# Sheet1_ESP32_Blynh.net
KiCad netlist of a schematic drawn in Altium Designer
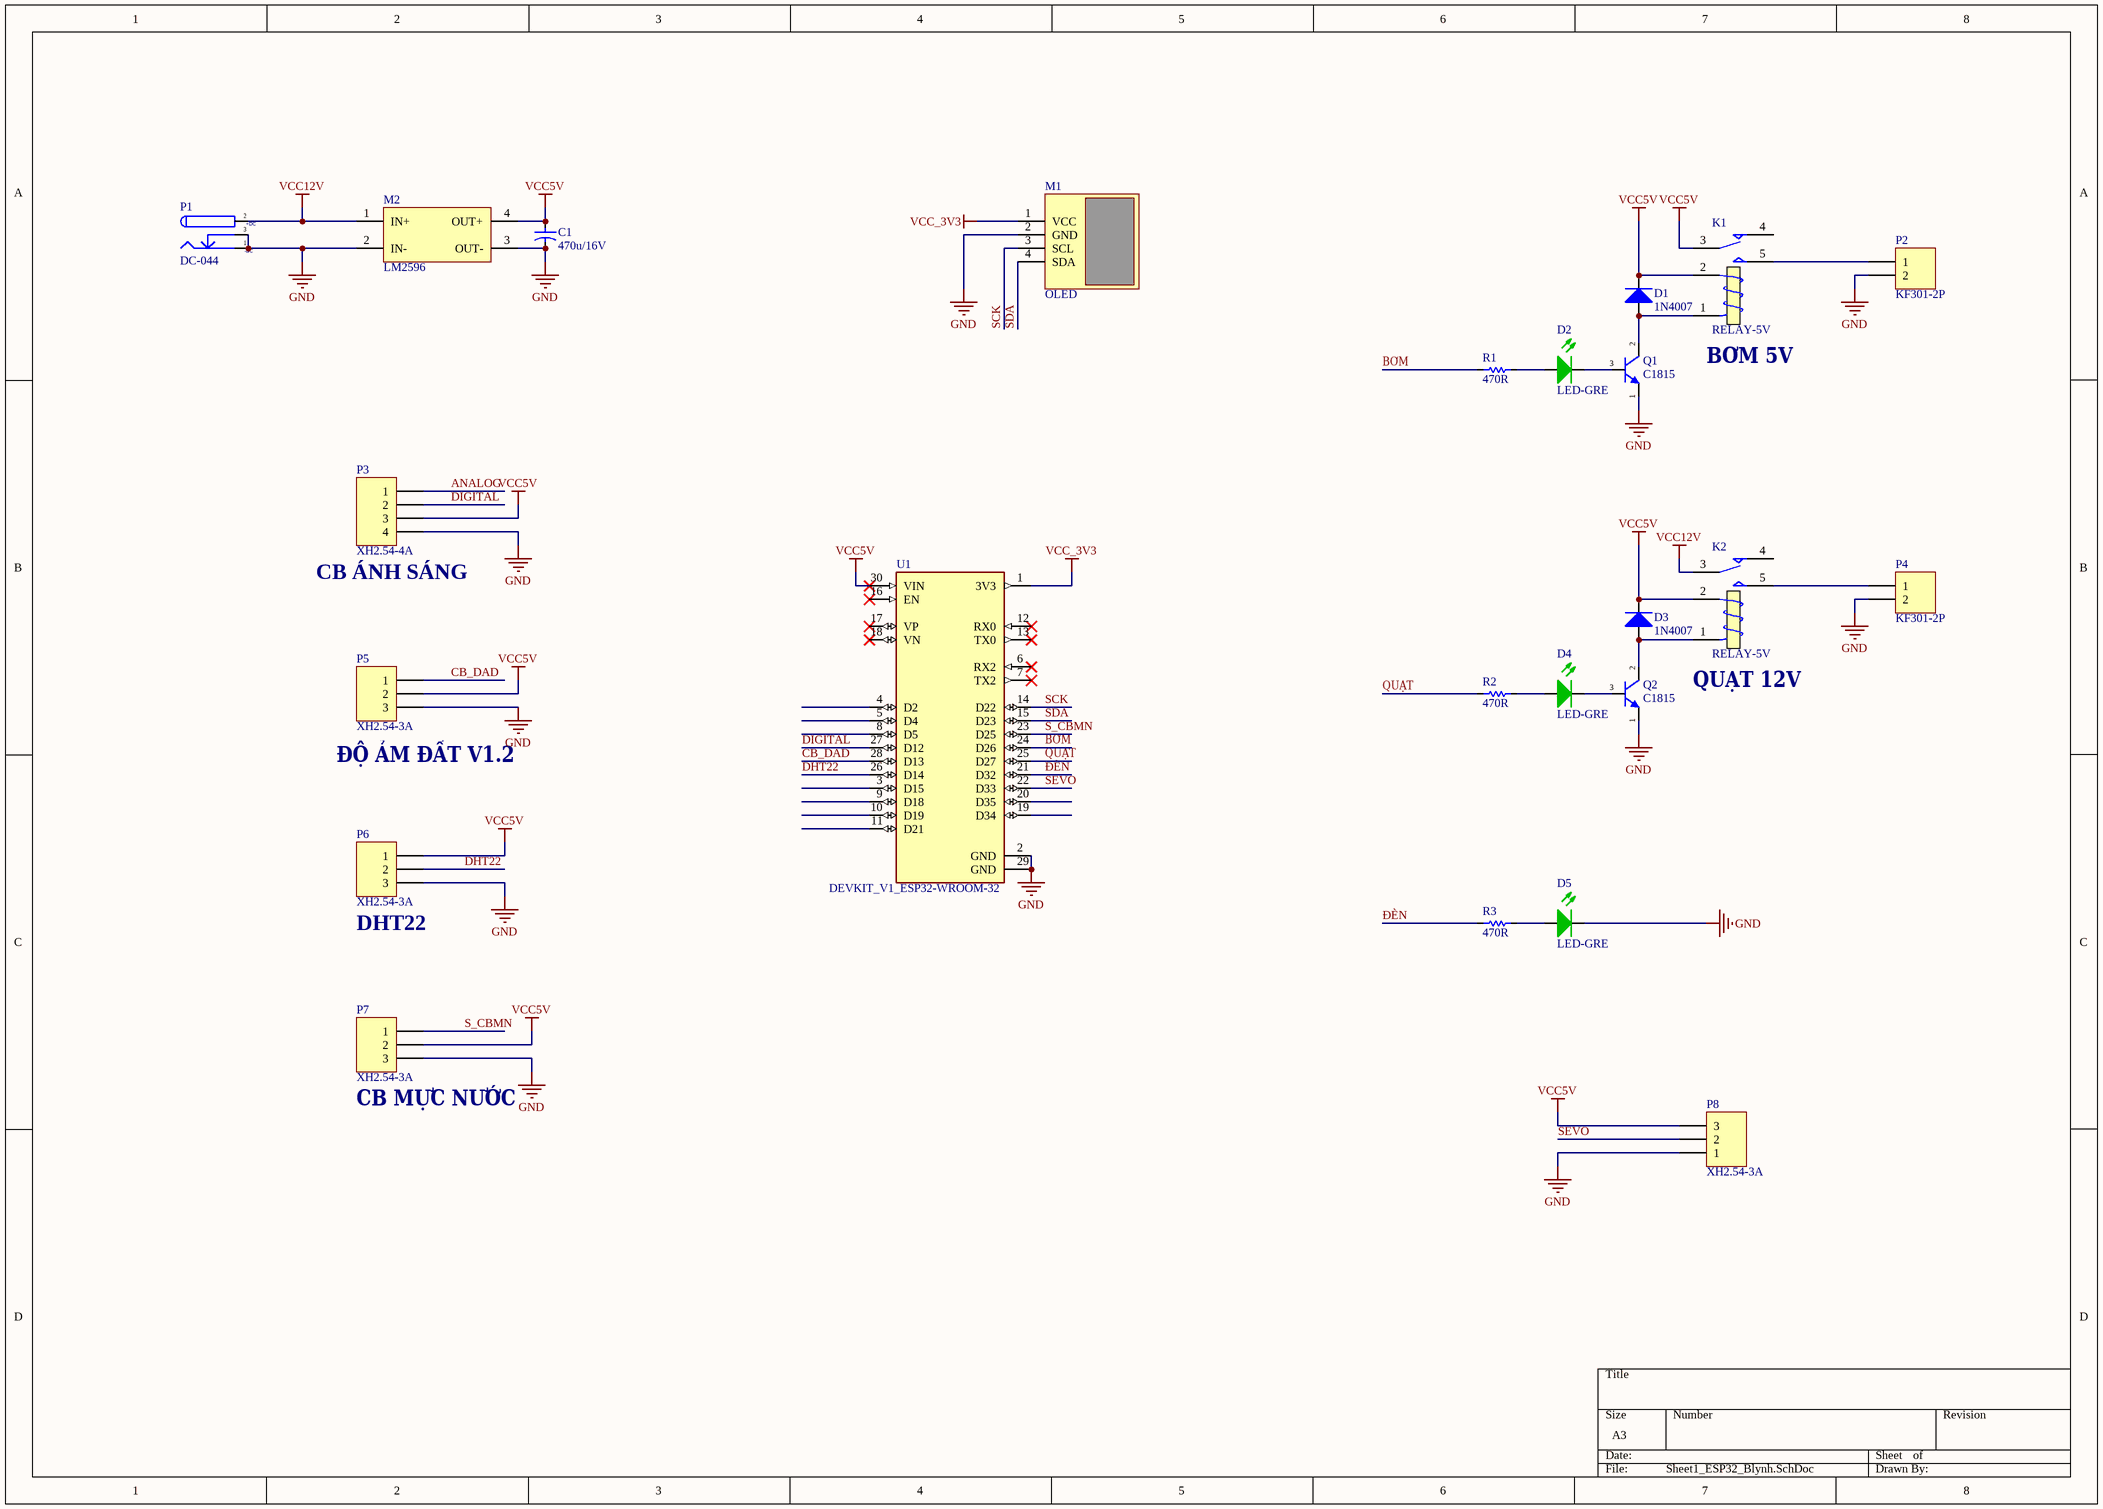
[diagram p0: Sheet1_ESP32_Blynh.SchDoc]

(export (version "E")
  (design (tool "Eeschema 10.0.6"))
  (components
    (comp (ref "C1")
      (value "470u/16V")
      (footprint "CAP 8x12x3.5")
      (description "470µF 16V Aluminum Capacitors Radial, Can 3000 Hrs @ 105°C")
      (libsource (lib "Capacitors-Smile-Lib") (part "470u/16V (8x12.5x3.5)"))
    )
    (comp (ref "D1")
      (value "1N4007")
      (footprint "DO41-300MIL")
      (description "1A 1000V Diode Standard")
      (libsource (lib "Diodes-Smile-Lib") (part "1N4007 DO41"))
    )
    (comp (ref "D2")
      (value "LED-GRE")
      (footprint "LED-3MM-G")
      (libsource (lib "LED-Smile-Lib") (part "LED-3MM-RED-LENS_GREEN"))
    )
    (comp (ref "D3")
      (value "1N4007")
      (footprint "DO41-300MIL")
      (description "1A 1000V Diode Standard")
      (libsource (lib "Diodes-Smile-Lib") (part "1N4007 DO41"))
    )
    (comp (ref "D4")
      (value "LED-GRE")
      (footprint "LED-3MM-G")
      (libsource (lib "LED-Smile-Lib") (part "LED-3MM-RED-LENS_GREEN"))
    )
    (comp (ref "D5")
      (value "LED-GRE")
      (footprint "LED-3MM-G")
      (libsource (lib "LED-Smile-Lib") (part "LED-3MM-RED-LENS_GREEN"))
    )
    (comp (ref "K1")
      (value "RELAY-5V")
      (footprint "RELAY 12V_112D1")
      (libsource (lib "Relay-Smile-Lib") (part "Relay SONGLE SRD-12VDC-SL-C 12V-10A(Type1)"))
    )
    (comp (ref "K2")
      (value "RELAY-5V")
      (footprint "RELAY 12V_112D1")
      (libsource (lib "Relay-Smile-Lib") (part "Relay SONGLE SRD-12VDC-SL-C 12V-10A(Type1)"))
    )
    (comp (ref "M1")
      (value "OLED")
      (footprint "OLED 0.96 I2C")
      (libsource (lib "Modules Smile Lib") (part "OLED 0.96 I2C"))
    )
    (comp (ref "M2")
      (value "LM2596")
      (footprint "LM2596 Module")
      (libsource (lib "Modules Smile Lib") (part "LM2596 Buck Module"))
    )
    (comp (ref "P1")
      (value "DC-044")
      (footprint "JACK DC 5.5-044")
      (description "JACK DC 044 5.5 2.1")
      (libsource (lib "Power Jack-Smile-Lib") (part "JACK DC-044"))
    )
    (comp (ref "P2")
      (value "KF301-2P")
      (footprint "KF301-2P")
      (libsource (lib "KF301-Connector-Smile-Lib") (part "KF301-2P"))
    )
    (comp (ref "P3")
      (value "XH2.54-4A")
      (footprint "XH2.54-4A")
      (libsource (lib "XH2.54-Smile-Lib") (part "XH2.54-4A"))
    )
    (comp (ref "P4")
      (value "KF301-2P")
      (footprint "KF301-2P")
      (libsource (lib "KF301-Connector-Smile-Lib") (part "KF301-2P"))
    )
    (comp (ref "P5")
      (value "XH2.54-3A")
      (footprint "XH2.54-3A")
      (libsource (lib "XH2.54-Smile-Lib") (part "XH2.54-3A"))
    )
    (comp (ref "P6")
      (value "XH2.54-3A")
      (footprint "XH2.54-3A")
      (libsource (lib "XH2.54-Smile-Lib") (part "XH2.54-3A"))
    )
    (comp (ref "P7")
      (value "XH2.54-3A")
      (footprint "XH2.54-3A")
      (libsource (lib "XH2.54-Smile-Lib") (part "XH2.54-3A"))
    )
    (comp (ref "P8") (value "XH2.54-3A") (footprint "XH2.54-3A") (libsource (lib "") (part "XH2.54-3A_1")))
    (comp (ref "Q1")
      (value "C1815")
      (footprint "TO-92")
      (description "TRANS NPN 50V 0.15A TO-92")
      (libsource (lib "BJT-Smile-Lib") (part "C1815-TO92"))
    )
    (comp (ref "Q2")
      (value "C1815")
      (footprint "TO-92")
      (description "TRANS NPN 50V 0.15A TO-92")
      (libsource (lib "BJT-Smile-Lib") (part "C1815-TO92"))
    )
    (comp (ref "R1")
      (value "470R")
      (footprint "R-300mil")
      (description "RES xxx OHM 1/4W 5% CARBON FILM")
      (libsource (lib "RES-0.25W-Smile-Lib") (part "R 1/4W 5%"))
    )
    (comp (ref "R2")
      (value "470R")
      (footprint "R-300mil")
      (description "RES xxx OHM 1/4W 5% CARBON FILM")
      (libsource (lib "RES-0.25W-Smile-Lib") (part "R 1/4W 5%"))
    )
    (comp (ref "R3")
      (value "470R")
      (footprint "R-300mil")
      (description "RES xxx OHM 1/4W 5% CARBON FILM")
      (libsource (lib "RES-0.25W-Smile-Lib") (part "R 1/4W 5%"))
    )
    (comp (ref "U1")
      (value "DEVKIT_V1_ESP32-WROOM-32")
      (footprint "MODULE_DEVKIT_V1_ESP32-WROOM-32")
      (description "WROOM-32 Development Board ESP32 ESP-32S WiFi Bluetooth Dev Module")
      (fields (field (name "MF") "Do it") (field (name "MP") "DEVKIT V1 ESP32-WROOM-32"))
      (libsource (lib "DEVKIT_V1_ESP32-WROOM-32") (part "DEVKIT_V1_ESP32-WROOM-32"))
    )
  )
  (nets
    (net (code "1") (name "/ANALOG") (class "Default")
      (node (ref "P3") (pin "1") (pinfunction "1_1") (pintype "passive"))
    )
    (net (code "2") (name "/BƠM") (class "Default")
      (node (ref "R1") (pin "2") (pinfunction "2_2") (pintype "passive"))
      (node (ref "U1") (pin "24") (pinfunction "D26_24") (pintype "bidirectional"))
    )
    (net (code "3") (name "/CB_DAD") (class "Default")
      (node (ref "P5") (pin "1") (pinfunction "1_1") (pintype "passive"))
      (node (ref "U1") (pin "28") (pinfunction "D13_28") (pintype "bidirectional"))
    )
    (net (code "4") (name "/DHT22") (class "Default")
      (node (ref "P6") (pin "2") (pinfunction "2_2") (pintype "passive"))
      (node (ref "U1") (pin "26") (pinfunction "D14_26") (pintype "bidirectional"))
    )
    (net (code "5") (name "/DIGITAL") (class "Default")
      (node (ref "P3") (pin "2") (pinfunction "2_2") (pintype "passive"))
      (node (ref "U1") (pin "27") (pinfunction "D12_27") (pintype "bidirectional"))
    )
    (net (code "6") (name "/QUẠT") (class "Default")
      (node (ref "R2") (pin "2") (pinfunction "2_2") (pintype "passive"))
      (node (ref "U1") (pin "25") (pinfunction "D27_25") (pintype "bidirectional"))
    )
    (net (code "7") (name "/SCK") (class "Default")
      (node (ref "M1") (pin "3") (pinfunction "SCL_3") (pintype "passive"))
      (node (ref "U1") (pin "14") (pinfunction "D22_14") (pintype "bidirectional"))
    )
    (net (code "8") (name "/SDA") (class "Default")
      (node (ref "M1") (pin "4") (pinfunction "SDA_4") (pintype "passive"))
      (node (ref "U1") (pin "15") (pinfunction "D23_15") (pintype "bidirectional"))
    )
    (net (code "9") (name "/SEVO") (class "Default")
      (node (ref "P8") (pin "2") (pinfunction "2_2") (pintype "passive"))
      (node (ref "U1") (pin "22") (pinfunction "D33_22") (pintype "bidirectional"))
    )
    (net (code "10") (name "/S_CBMN") (class "Default")
      (node (ref "P7") (pin "1") (pinfunction "1_1") (pintype "passive"))
      (node (ref "U1") (pin "23") (pinfunction "D25_23") (pintype "bidirectional"))
    )
    (net (code "11") (name "/ĐÈN") (class "Default")
      (node (ref "R3") (pin "2") (pinfunction "2_2") (pintype "passive"))
      (node (ref "U1") (pin "21") (pinfunction "D32_21") (pintype "bidirectional"))
    )
    (net (code "12") (name "GND") (class "Default")
      (node (ref "C1") (pin "2") (pinfunction "2_2") (pintype "passive"))
      (node (ref "D5") (pin "2") (pinfunction "K_2") (pintype "passive"))
      (node (ref "M1") (pin "2") (pinfunction "GND_2") (pintype "passive"))
      (node (ref "M2") (pin "2") (pinfunction "IN-_2") (pintype "passive"))
      (node (ref "M2") (pin "3") (pinfunction "OUT-_3") (pintype "passive"))
      (node (ref "P1") (pin "1") (pinfunction "1_1") (pintype "power_in"))
      (node (ref "P1") (pin "3") (pinfunction "3_3") (pintype "power_in"))
      (node (ref "P2") (pin "2") (pinfunction "2_2") (pintype "passive"))
      (node (ref "P3") (pin "4") (pinfunction "4_4") (pintype "passive"))
      (node (ref "P4") (pin "2") (pinfunction "2_2") (pintype "passive"))
      (node (ref "P5") (pin "3") (pinfunction "3_3") (pintype "passive"))
      (node (ref "P6") (pin "3") (pinfunction "3_3") (pintype "passive"))
      (node (ref "P7") (pin "3") (pinfunction "3_3") (pintype "passive"))
      (node (ref "P8") (pin "1") (pinfunction "1_1") (pintype "passive"))
      (node (ref "Q1") (pin "1") (pinfunction "E_1") (pintype "passive"))
      (node (ref "Q2") (pin "1") (pinfunction "E_1") (pintype "passive"))
      (node (ref "U1") (pin "2") (pinfunction "GND_2") (pintype "power_in"))
      (node (ref "U1") (pin "29") (pinfunction "GND_29") (pintype "power_in"))
    )
    (net (code "13") (name "Net-(D1-A)") (class "Default")
      (node (ref "D1") (pin "1") (pinfunction "A_1") (pintype "passive"))
      (node (ref "K1") (pin "1") (pinfunction "T2_1") (pintype "passive"))
      (node (ref "Q1") (pin "2") (pinfunction "C_2") (pintype "passive"))
    )
    (net (code "14") (name "Net-(D2-A)") (class "Default")
      (node (ref "D2") (pin "1") (pinfunction "A_1") (pintype "passive"))
      (node (ref "R1") (pin "1") (pinfunction "1_1") (pintype "passive"))
    )
    (net (code "15") (name "Net-(D2-K)") (class "Default")
      (node (ref "D2") (pin "2") (pinfunction "K_2") (pintype "passive"))
      (node (ref "Q1") (pin "3") (pinfunction "B_3") (pintype "passive"))
    )
    (net (code "16") (name "Net-(D3-A)") (class "Default")
      (node (ref "D3") (pin "1") (pinfunction "A_1") (pintype "passive"))
      (node (ref "K2") (pin "1") (pinfunction "T2_1") (pintype "passive"))
      (node (ref "Q2") (pin "2") (pinfunction "C_2") (pintype "passive"))
    )
    (net (code "17") (name "Net-(D4-A)") (class "Default")
      (node (ref "D4") (pin "1") (pinfunction "A_1") (pintype "passive"))
      (node (ref "R2") (pin "1") (pinfunction "1_1") (pintype "passive"))
    )
    (net (code "18") (name "Net-(D4-K)") (class "Default")
      (node (ref "D4") (pin "2") (pinfunction "K_2") (pintype "passive"))
      (node (ref "Q2") (pin "3") (pinfunction "B_3") (pintype "passive"))
    )
    (net (code "19") (name "Net-(D5-A)") (class "Default")
      (node (ref "D5") (pin "1") (pinfunction "A_1") (pintype "passive"))
      (node (ref "R3") (pin "1") (pinfunction "1_1") (pintype "passive"))
    )
    (net (code "20") (name "Net-(K1-NO)") (class "Default")
      (node (ref "K1") (pin "5") (pinfunction "NO_5") (pintype "passive"))
      (node (ref "P2") (pin "1") (pinfunction "1_1") (pintype "passive"))
    )
    (net (code "21") (name "Net-(K2-NO)") (class "Default")
      (node (ref "K2") (pin "5") (pinfunction "NO_5") (pintype "passive"))
      (node (ref "P4") (pin "1") (pinfunction "1_1") (pintype "passive"))
    )
    (net (code "22") (name "VCC5V") (class "Default")
      (node (ref "C1") (pin "1") (pinfunction "1_1") (pintype "passive"))
      (node (ref "D1") (pin "2") (pinfunction "K_2") (pintype "passive"))
      (node (ref "D3") (pin "2") (pinfunction "K_2") (pintype "passive"))
      (node (ref "K1") (pin "2") (pinfunction "T1_2") (pintype "passive"))
      (node (ref "K1") (pin "3") (pinfunction "COM_3") (pintype "passive"))
      (node (ref "K2") (pin "2") (pinfunction "T1_2") (pintype "passive"))
      (node (ref "M2") (pin "4") (pinfunction "OUT+_4") (pintype "passive"))
      (node (ref "P3") (pin "3") (pinfunction "3_3") (pintype "passive"))
      (node (ref "P5") (pin "2") (pinfunction "2_2") (pintype "passive"))
      (node (ref "P6") (pin "1") (pinfunction "1_1") (pintype "passive"))
      (node (ref "P7") (pin "2") (pinfunction "2_2") (pintype "passive"))
      (node (ref "P8") (pin "3") (pinfunction "3_3") (pintype "passive"))
      (node (ref "U1") (pin "30") (pinfunction "VIN_30") (pintype "input"))
    )
    (net (code "23") (name "VCC12V") (class "Default")
      (node (ref "K2") (pin "3") (pinfunction "COM_3") (pintype "passive"))
      (node (ref "M2") (pin "1") (pinfunction "IN+_1") (pintype "passive"))
      (node (ref "P1") (pin "2") (pinfunction "2_2") (pintype "power_in"))
    )
    (net (code "24") (name "VCC_3V3") (class "Default")
      (node (ref "M1") (pin "1") (pinfunction "VCC_1") (pintype "passive"))
      (node (ref "U1") (pin "1") (pinfunction "3V3_1") (pintype "output"))
    )
    (net (code "25") (name "unconnected-(K1-NC-Pad4)") (class "Default")
      (node (ref "K1") (pin "4") (pinfunction "NC_4") (pintype "passive"))
    )
    (net (code "26") (name "unconnected-(K2-NC-Pad4)") (class "Default")
      (node (ref "K2") (pin "4") (pinfunction "NC_4") (pintype "passive"))
    )
    (net (code "27") (name "unconnected-(U1-D2-Pad4)") (class "Default")
      (node (ref "U1") (pin "4") (pinfunction "D2_4") (pintype "bidirectional"))
    )
    (net (code "28") (name "unconnected-(U1-D4-Pad5)") (class "Default")
      (node (ref "U1") (pin "5") (pinfunction "D4_5") (pintype "bidirectional"))
    )
    (net (code "29") (name "unconnected-(U1-D5-Pad8)") (class "Default")
      (node (ref "U1") (pin "8") (pinfunction "D5_8") (pintype "bidirectional"))
    )
    (net (code "30") (name "unconnected-(U1-D15-Pad3)") (class "Default")
      (node (ref "U1") (pin "3") (pinfunction "D15_3") (pintype "bidirectional"))
    )
    (net (code "31") (name "unconnected-(U1-D18-Pad9)") (class "Default")
      (node (ref "U1") (pin "9") (pinfunction "D18_9") (pintype "bidirectional"))
    )
    (net (code "32") (name "unconnected-(U1-D19-Pad10)") (class "Default")
      (node (ref "U1") (pin "10") (pinfunction "D19_10") (pintype "bidirectional"))
    )
    (net (code "33") (name "unconnected-(U1-D21-Pad11)") (class "Default")
      (node (ref "U1") (pin "11") (pinfunction "D21_11") (pintype "bidirectional"))
    )
    (net (code "34") (name "unconnected-(U1-D34-Pad19)") (class "Default")
      (node (ref "U1") (pin "19") (pinfunction "D34_19") (pintype "bidirectional"))
    )
    (net (code "35") (name "unconnected-(U1-D35-Pad20)") (class "Default")
      (node (ref "U1") (pin "20") (pinfunction "D35_20") (pintype "bidirectional"))
    )
    (net (code "36") (name "unconnected-(U1-EN-Pad16)") (class "Default")
      (node (ref "U1") (pin "16") (pinfunction "EN_16") (pintype "input+no_connect"))
    )
    (net (code "37") (name "unconnected-(U1-RX0-Pad12)") (class "Default")
      (node (ref "U1") (pin "12") (pinfunction "RX0_12") (pintype "input+no_connect"))
    )
    (net (code "38") (name "unconnected-(U1-RX2-Pad6)") (class "Default")
      (node (ref "U1") (pin "6") (pinfunction "RX2_6") (pintype "input+no_connect"))
    )
    (net (code "39") (name "unconnected-(U1-TX0-Pad13)") (class "Default")
      (node (ref "U1") (pin "13") (pinfunction "TX0_13") (pintype "output+no_connect"))
    )
    (net (code "40") (name "unconnected-(U1-TX2-Pad7)") (class "Default")
      (node (ref "U1") (pin "7") (pinfunction "TX2_7") (pintype "output+no_connect"))
    )
    (net (code "41") (name "unconnected-(U1-VN-Pad18)") (class "Default")
      (node (ref "U1") (pin "18") (pinfunction "VN_18") (pintype "bidirectional+no_connect"))
    )
    (net (code "42") (name "unconnected-(U1-VP-Pad17)") (class "Default")
      (node (ref "U1") (pin "17") (pinfunction "VP_17") (pintype "bidirectional+no_connect"))
    )
  )
)
